# Power.net
KiCad netlist of a schematic drawn in Altium Designer
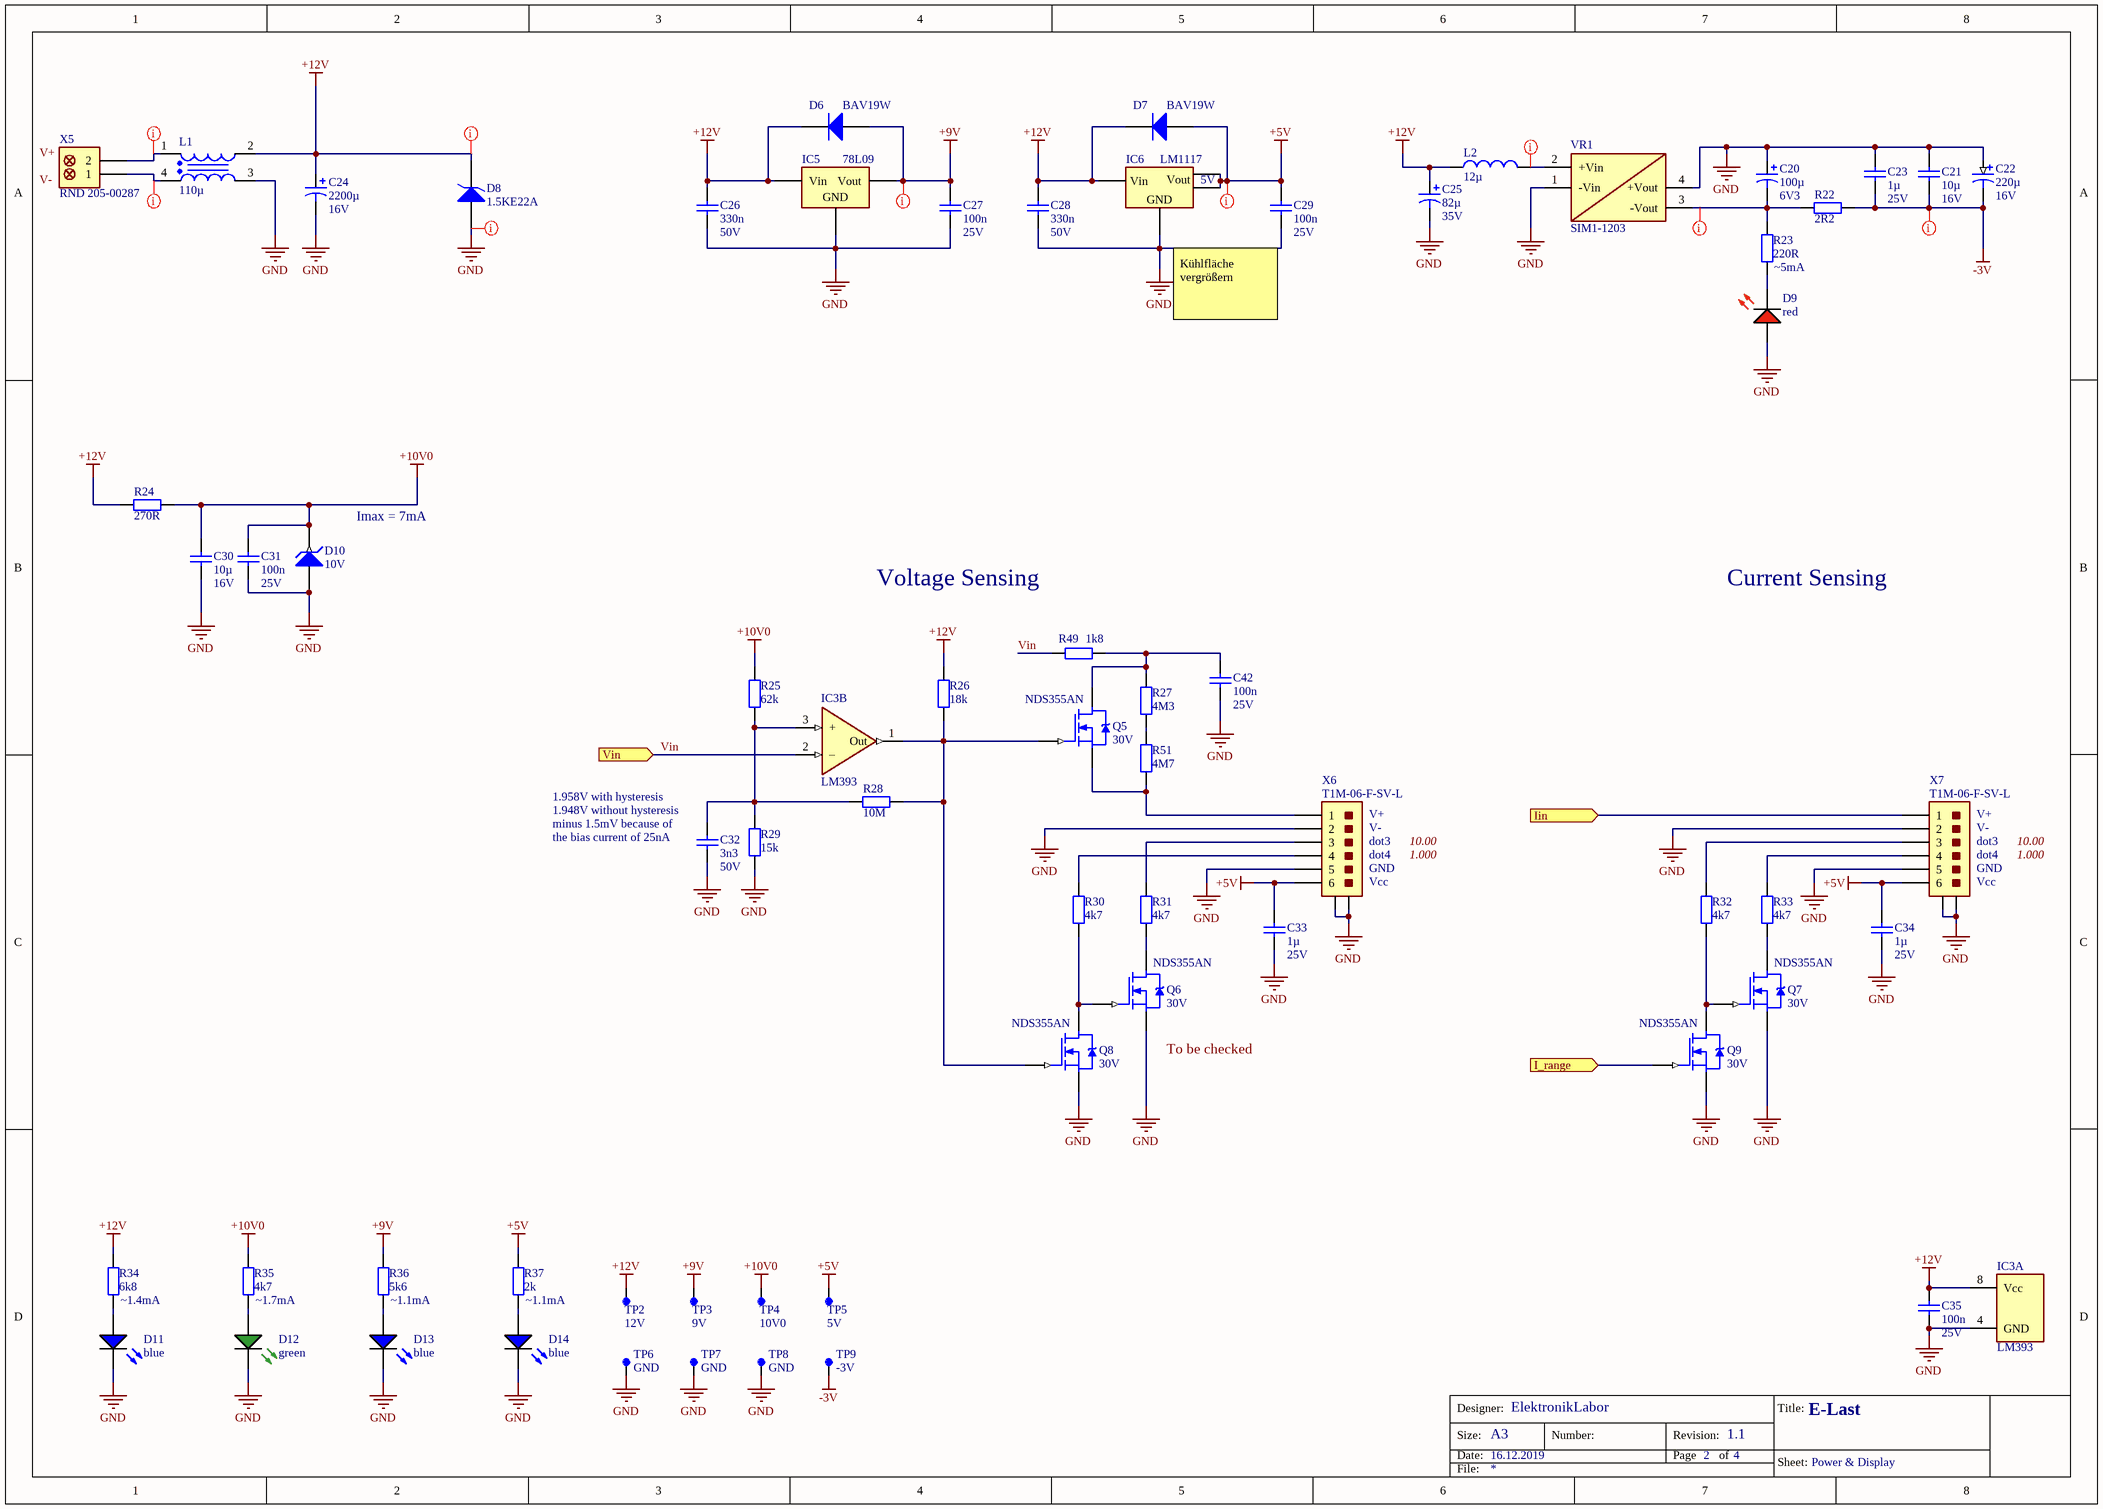
[diagram p0: Power.SchDoc]

(export (version "E")
  (design (tool "Eeschema 10.0.6"))
  (components
    (comp (ref "C20")
      (value "100µ")
      (footprint "Cap ELCO 6.3x6 mm")
      (description "Cap Elco 100µ Radial")
      (fields
        (field (name "MANUFACTURER") "Nichicon")
        (field (name "PARTNUMBER") "UMA0J101MDD")
        (field (name "VOLTAGE") "6V3")
        (field (name "COMPONENTLINK1URL") "G:\\Daten\\Datenblätter\\Kondensatoren\\Nichicon_UMA.pdf")
      )
      (libsource (lib "SchLibrary") (part "Cap Pol2 100µ"))
    )
    (comp (ref "C21")
      (value "10µ")
      (footprint "C_1206")
      (description "Cap Ceramic 1206 10µ 16V")
      (fields
        (field (name "PARTNUMBER") "CL31B106MOHNNNE")
        (field (name "MANUFACTURER") "Samsung")
        (field (name "VOLTAGE") "16V")
      )
      (libsource (lib "CustomLib") (part "C-Cer 1206 16V 10µ"))
    )
    (comp (ref "C22")
      (value "220µ")
      (footprint "Cap Tantal E (2917)")
      (description "Cap Tantal 220µ 16V SMD")
      (fields
        (field (name "MANUFACTURER") "AVX")
        (field (name "PARTNUMBER") "TPSE227*016#0100")
        (field (name "VOLTAGE") "16V")
        (field (name "COMPONENTLINK1URL") "G:\\Daten\\Datenblätter\\Kondensatoren\\AVX_Tantal_TPS.pdf")
      )
      (libsource (lib "CustomLib") (part "Cap Tantal 220µ"))
    )
    (comp (ref "C23")
      (value "1µ")
      (footprint "C_0805")
      (description "Cap Ceramic 0805 1µ 25V")
      (fields
        (field (name "MANUFACTURER") "Samsung")
        (field (name "PARTNUMBER") "CL21B105KAFNNNE")
        (field (name "VOLTAGE") "25V")
      )
      (libsource (lib "SchLibrary") (part "C-Cer 0805 1µ"))
    )
    (comp (ref "C24")
      (value "2200µ")
      (footprint "Cap ELCO 12.5x20 mm")
      (description "Cap Elco 2200µ 16V THT Radial")
      (fields
        (field (name "MANUFACTURER") "Rubycon")
        (field (name "PARTNUMBER") "UFW1C222MHD")
        (field (name "VOLTAGE") "16V")
        (field (name "COMPONENTLINK1URL") "G:\\Daten\\Datenblätter\\Kondensatoren\\Nichicon_UFW.pdf")
      )
      (libsource (lib "SchLibrary") (part "Cap Pol 2200µ 16V"))
    )
    (comp (ref "C25")
      (value "82µ")
      (footprint "Cap ELCO 6.3x15 mm")
      (description "Cap Elco 82µ Radial")
      (fields
        (field (name "MANUFACTURER") "Nippon Chemi-Con")
        (field (name "PARTNUMBER") "ELXY350ETD820MF15D")
        (field (name "VOLTAGE") "35V")
        (field (name "COMPONENTLINK1URL") "G:\\Daten\\Datenblätter\\Kondensatoren\\Chemi-Con_LXY.pdf")
      )
      (libsource (lib "SchLibrary") (part "Cap Pol2 82µ"))
    )
    (comp (ref "C26")
      (value "330n")
      (footprint "C_0805")
      (description "Cap Ceramic 0805 330n 50V")
      (fields
        (field (name "MANUFACTURER") "Samsung")
        (field (name "PARTNUMBER") "CL21B334KBFNNNE")
        (field (name "VOLTAGE") "50V")
      )
      (libsource (lib "SchLibrary") (part "C-Cer 0805 330n"))
    )
    (comp (ref "C27")
      (value "100n")
      (footprint "C_0805")
      (description "Cap Ceramic 0805 100n 25V")
      (fields (field (name "MANUFACTURER") "generic") (field (name "VOLTAGE") "25V"))
      (libsource (lib "CustomLib") (part "C-Cer 0805 100n"))
    )
    (comp (ref "C28")
      (value "330n")
      (footprint "C_0805")
      (description "Cap Ceramic 0805 330n 50V")
      (fields
        (field (name "MANUFACTURER") "Samsung")
        (field (name "PARTNUMBER") "CL21B334KBFNNNE")
        (field (name "VOLTAGE") "50V")
      )
      (libsource (lib "SchLibrary") (part "C-Cer 0805 330n"))
    )
    (comp (ref "C29")
      (value "100n")
      (footprint "C_0805")
      (description "Cap Ceramic 0805 100n 25V")
      (fields (field (name "MANUFACTURER") "generic") (field (name "VOLTAGE") "25V"))
      (libsource (lib "CustomLib") (part "C-Cer 0805 100n"))
    )
    (comp (ref "C30")
      (value "10µ")
      (footprint "C_1206")
      (description "Cap Ceramic 1206 10µ 16V")
      (fields
        (field (name "PARTNUMBER") "CL31B106MOHNNNE")
        (field (name "MANUFACTURER") "Samsung")
        (field (name "VOLTAGE") "16V")
      )
      (libsource (lib "CustomLib") (part "C-Cer 1206 16V 10µ"))
    )
    (comp (ref "C31")
      (value "100n")
      (footprint "C_0805")
      (description "Cap Ceramic 0805 100n 25V")
      (fields (field (name "MANUFACTURER") "generic") (field (name "VOLTAGE") "25V"))
      (libsource (lib "SchLibrary") (part "C-Cer 0805 100n"))
    )
    (comp (ref "C32")
      (value "3n3")
      (footprint "C_0805")
      (description "Cap Ceramic 0805 3n3 50V")
      (fields (field (name "MANUFACTURER") "generic") (field (name "VOLTAGE") "50V"))
      (libsource (lib "CustomLib") (part "C-Cer 0805 3n3"))
    )
    (comp (ref "C33")
      (value "1µ")
      (footprint "C_0805")
      (description "Cap Ceramic 0805 1µ 25V")
      (fields
        (field (name "MANUFACTURER") "Samsung")
        (field (name "PARTNUMBER") "CL21B105KAFNNNE")
        (field (name "VOLTAGE") "25V")
      )
      (libsource (lib "SchLibrary") (part "C-Cer 0805 1µ"))
    )
    (comp (ref "C34")
      (value "1µ")
      (footprint "C_0805")
      (description "Cap Ceramic 0805 1µ 25V")
      (fields
        (field (name "MANUFACTURER") "Samsung")
        (field (name "PARTNUMBER") "CL21B105KAFNNNE")
        (field (name "VOLTAGE") "25V")
      )
      (libsource (lib "SchLibrary") (part "C-Cer 0805 1µ"))
    )
    (comp (ref "C35")
      (value "100n")
      (footprint "C_0805")
      (description "Cap Ceramic 0805 100n 25V")
      (fields (field (name "MANUFACTURER") "generic") (field (name "VOLTAGE") "25V"))
      (libsource (lib "SchLibrary") (part "C-Cer 0805 100n"))
    )
    (comp (ref "C42")
      (value "100n")
      (footprint "C_0805")
      (description "Cap Ceramic 0805 100n 25V")
      (fields (field (name "MANUFACTURER") "generic") (field (name "VOLTAGE") "25V"))
      (libsource (lib "SchLibrary") (part "C-Cer 0805 100n"))
    )
    (comp (ref "D6")
      (value "BAV19W")
      (footprint "SOD-123")
      (description "Diode, Fast, 400mA, SOD-123, SMD")
      (fields
        (field (name "MANUFACTURER") "Diodes")
        (field (name "PARTNUMBER") "BAV19W-E3-08")
        (field (name "COMPONENTLINK1URL") "G:\\Daten\\Datenblätter\\Dioden\\BAV19W.pdf")
      )
      (libsource (lib "CustomLib") (part "Diode BAV19W"))
    )
    (comp (ref "D7")
      (value "BAV19W")
      (footprint "SOD-123")
      (description "Diode, Fast, 400mA, SOD-123, SMD")
      (fields
        (field (name "MANUFACTURER") "Diodes")
        (field (name "PARTNUMBER") "BAV19W-E3-08")
        (field (name "COMPONENTLINK1URL") "G:\\Daten\\Datenblätter\\Dioden\\BAV19W.pdf")
      )
      (libsource (lib "CustomLib") (part "Diode BAV19W"))
    )
    (comp (ref "D8")
      (value "1.5KE22A")
      (footprint "DO-201AD Vert")
      (description "Diode, TVS, Uni, 22V, CB429, THT")
      (fields
        (field (name "MANUFACTURER") "ST")
        (field (name "VOLTAGE") "18.8V")
        (field (name "COMPONENTLINK1URL") "G:\\Daten\\Datenblätter\\Dioden\\1_5KE22A_TVS.pdf")
      )
      (libsource (lib "CustomLib") (part "Diode 1.5KE22A"))
    )
    (comp (ref "D9")
      (value "red")
      (footprint "LED 0805 SMD WL-SMCW")
      (description "LED Red 0805 SMD")
      (fields
        (field (name "MANUFACTURER") "Würth Elektronik")
        (field (name "PARTNUMBER") "150080SS75000")
        (field (name "COMPONENTLINK1URL") "G:\\Daten\\Datenblätter\\LED\\0805_red_150080SS75000.pdf")
      )
      (libsource (lib "SchLibrary") (part "LED Red 0805 SMD"))
    )
    (comp (ref "D10")
      (value "10V")
      (footprint "SOT23_N")
      (description "V-Ref LM4040AIM3-10.0")
      (fields
        (field (name "PARTNUMBER") "LM4040AIM3-10.0/NOPB")
        (field (name "MANUFACTURER") "Texas Instruments")
        (field (name "COMPONENTLINK1URL") "G:\\Daten\\Datenblätter\\Spg.-Referenz\\TI_LM4040-N.pdf")
      )
      (libsource (lib "SchLibrary") (part "V-Ref LM4040AIM3-10.0"))
    )
    (comp (ref "D11")
      (value "blue")
      (footprint "LED 0805 SMD WL-SMCW")
      (description "LED Blue 0805 SMD")
      (fields
        (field (name "MANUFACTURER") "Würth Elektronik")
        (field (name "PARTNUMBER") "150080BS75000")
        (field (name "COMPONENTLINK1URL") "G:\\Daten\\Datenblätter\\LED\\0805_blue_150080BS75000.pdf")
      )
      (libsource (lib "SchLibrary") (part "LED Blue 0805 SMD"))
    )
    (comp (ref "D12")
      (value "green")
      (footprint "LED 0805 SMD WL-SMCW")
      (description "LED Green 0805 SMD")
      (fields (field (name "PARTNUMBER") "Generic") (field (name "VOLTAGE") "1.886V"))
      (libsource (lib "CustomLib") (part "LED Green 0805 SMD"))
    )
    (comp (ref "D13")
      (value "blue")
      (footprint "LED 0805 SMD WL-SMCW")
      (description "LED Blue 0805 SMD")
      (fields
        (field (name "MANUFACTURER") "Würth Elektronik")
        (field (name "PARTNUMBER") "150080BS75000")
        (field (name "COMPONENTLINK1URL") "G:\\Daten\\Datenblätter\\LED\\0805_blue_150080BS75000.pdf")
      )
      (libsource (lib "SchLibrary") (part "LED Blue 0805 SMD"))
    )
    (comp (ref "D14")
      (value "blue")
      (footprint "LED 0805 SMD WL-SMCW")
      (description "LED Blue 0805 SMD")
      (fields
        (field (name "MANUFACTURER") "Würth Elektronik")
        (field (name "PARTNUMBER") "150080BS75000")
        (field (name "COMPONENTLINK1URL") "G:\\Daten\\Datenblätter\\LED\\0805_blue_150080BS75000.pdf")
      )
      (libsource (lib "SchLibrary") (part "LED Blue 0805 SMD"))
    )
    (comp (ref "IC3")
      (value "LM393")
      (footprint "SOIC8_N")
      (description "Comparator LM393DT 2x")
      (fields
        (field (name "MANUFACTURER") "ST")
        (field (name "PARTNUMBER") "LM393DT")
        (field (name "COMPONENTLINK1URL") "G:\\Daten\\Datenblätter\\Komparatoren\\ST_LM393.pdf")
      )
      (libsource (lib "SchLibrary") (part "LM393DT"))
    )
    (comp (ref "IC5")
      (value "78L09")
      (footprint "TO-92A")
      (description "Voltage Regulator 9V")
      (fields
        (field (name "MANUFACTURER") "ST")
        (field (name "PARTNUMBER") "L78L09ACZ")
        (field (name "COMPONENTLINK1URL") "G:\\Daten\\Datenblätter\\Spannungsregler\\78L09_ST.pdf")
      )
      (libsource (lib "CustomLib") (part "Volt Reg 78L09 TO92"))
    )
    (comp (ref "IC6")
      (value "LM1117")
      (footprint "SOT-223")
      (description "Voltage Regulator 5V SOT-223")
      (fields
        (field (name "MANUFACTURER") "Texas Instruments")
        (field (name "PARTNUMBER") "L7805CV")
        (field (name "VOLTAGE") "5V")
        (field (name "COMPONENTLINK1URL") "G:\\Daten\\Datenblätter\\Spannungsregler\\LM1117.pdf")
      )
      (libsource (lib "CustomLib") (part "Volt Reg LM1117MPX-5.0 SOT-223"))
    )
    (comp (ref "L1")
      (value "110µ")
      (footprint "CMC WE-CMB Type S")
      (description "Common Mode Choke, WE-CMB Type S, 110 uH")
      (fields (field (name "MANUFACTURER") "Würth Elektronik") (field (name "PARTNUMBER") "744842311"))
      (libsource (lib "CustomLib") (part "CMC 110µ"))
    )
    (comp (ref "L2")
      (value "12µ")
      (footprint "WE-GFH 4532")
      (description "Inductor 12µ 7447669112 SMD")
      (fields
        (field (name "PARTNUMBER") "7447669112")
        (field (name "MANUFACTURER") "Würth Elektronik")
        (field (name "COMPONENTLINK1URL") "G:\\Daten\\Datenblätter\\Inductors\\WE_7447669112_12µ.pdf")
      )
      (libsource (lib "SchLibrary") (part "Inductor 12µ"))
    )
    (comp (ref "Q5")
      (value "NDS355AN")
      (footprint "SOT23_N - n-MOS")
      (description "Transistor n-MOS SOT-23 30V Vgs=20V")
      (fields
        (field (name "MANUFACTURER") "ON Semiconductor")
        (field (name "VOLTAGE") "30V")
        (field (name "COMPONENTLINK1URL") "G:\\Daten\\Datenblätter\\Transistoren\\nMOS_NDS355AN.pdf")
      )
      (libsource (lib "SchLibrary") (part "Transistor n-MOS NDS355AN"))
    )
    (comp (ref "Q6")
      (value "NDS355AN")
      (footprint "SOT23_N - n-MOS")
      (description "Transistor n-MOS SOT-23 30V Vgs=20V")
      (fields
        (field (name "MANUFACTURER") "ON Semiconductor")
        (field (name "VOLTAGE") "30V")
        (field (name "COMPONENTLINK1URL") "G:\\Daten\\Datenblätter\\Transistoren\\nMOS_NDS355AN.pdf")
      )
      (libsource (lib "SchLibrary") (part "Transistor n-MOS NDS355AN"))
    )
    (comp (ref "Q7")
      (value "NDS355AN")
      (footprint "SOT23_N - n-MOS")
      (description "Transistor n-MOS SOT-23 30V Vgs=20V")
      (fields
        (field (name "MANUFACTURER") "ON Semiconductor")
        (field (name "VOLTAGE") "30V")
        (field (name "COMPONENTLINK1URL") "G:\\Daten\\Datenblätter\\Transistoren\\nMOS_NDS355AN.pdf")
      )
      (libsource (lib "SchLibrary") (part "Transistor n-MOS NDS355AN"))
    )
    (comp (ref "Q8")
      (value "NDS355AN")
      (footprint "SOT23_N - n-MOS")
      (description "Transistor n-MOS SOT-23 30V Vgs=20V")
      (fields
        (field (name "MANUFACTURER") "ON Semiconductor")
        (field (name "VOLTAGE") "30V")
        (field (name "COMPONENTLINK1URL") "G:\\Daten\\Datenblätter\\Transistoren\\nMOS_NDS355AN.pdf")
      )
      (libsource (lib "SchLibrary") (part "Transistor n-MOS NDS355AN"))
    )
    (comp (ref "Q9")
      (value "NDS355AN")
      (footprint "SOT23_N - n-MOS")
      (description "Transistor n-MOS SOT-23 30V Vgs=20V")
      (fields
        (field (name "MANUFACTURER") "ON Semiconductor")
        (field (name "VOLTAGE") "30V")
        (field (name "COMPONENTLINK1URL") "G:\\Daten\\Datenblätter\\Transistoren\\nMOS_NDS355AN.pdf")
      )
      (libsource (lib "SchLibrary") (part "Transistor n-MOS NDS355AN"))
    )
    (comp (ref "R22")
      (value "2R2")
      (footprint "Res 0805")
      (description "Resistor 0805 2R2")
      (fields (field (name "MANUFACTURER") "generic") (field (name "POWER") "0.125W"))
      (libsource (lib "SchLibrary") (part "Res 0805 2R2"))
    )
    (comp (ref "R23")
      (value "220R")
      (footprint "Res 0805")
      (description "Resistor 0805 220R")
      (fields (field (name "MANUFACTURER") "generic") (field (name "POWER") "0.125W"))
      (libsource (lib "SchLibrary") (part "Res 0805 220R"))
    )
    (comp (ref "R24")
      (value "270R")
      (footprint "Res 0805")
      (description "Resistor 0805 270R")
      (fields (field (name "MANUFACTURER") "generic") (field (name "POWER") "0.125W"))
      (libsource (lib "SchLibrary") (part "Res 0805 270R"))
    )
    (comp (ref "R25")
      (value "62k")
      (footprint "Res 0805")
      (description "Resistor 0805 62k")
      (fields (field (name "MANUFACTURER") "generic") (field (name "POWER") "0.125W"))
      (libsource (lib "SchLibrary") (part "Res 0805 62k"))
    )
    (comp (ref "R26")
      (value "18k")
      (footprint "Res 0805")
      (description "Resistor 0805 18k")
      (fields (field (name "MANUFACTURER") "generic") (field (name "POWER") "0.125W"))
      (libsource (lib "SchLibrary") (part "Res 0805 18k"))
    )
    (comp (ref "R27")
      (value "4M3")
      (footprint "Res 0805")
      (description "Resistor 0805 4M3")
      (fields (field (name "MANUFACTURER") "generic") (field (name "POWER") "0.125W"))
      (libsource (lib "CustomLib") (part "Res 0805 4M3"))
    )
    (comp (ref "R28")
      (value "10M")
      (footprint "Res 0805")
      (description "Resistor 0805 10M")
      (fields (field (name "MANUFACTURER") "generic") (field (name "POWER") "0.125W"))
      (libsource (lib "SchLibrary") (part "Res 0805 10M"))
    )
    (comp (ref "R29")
      (value "15k")
      (footprint "Res 0805")
      (description "Resistor 0805 15k")
      (fields (field (name "MANUFACTURER") "generic") (field (name "POWER") "0.125W"))
      (libsource (lib "SchLibrary") (part "Res 0805 15k"))
    )
    (comp (ref "R30")
      (value "4k7")
      (footprint "Res 0805")
      (description "Resistor 0805 4k7")
      (fields (field (name "MANUFACTURER") "generic") (field (name "POWER") "0.125W"))
      (libsource (lib "SchLibrary") (part "Res 0805 4k7"))
    )
    (comp (ref "R31")
      (value "4k7")
      (footprint "Res 0805")
      (description "Resistor 0805 4k7")
      (fields (field (name "MANUFACTURER") "generic") (field (name "POWER") "0.125W"))
      (libsource (lib "SchLibrary") (part "Res 0805 4k7"))
    )
    (comp (ref "R32")
      (value "4k7")
      (footprint "Res 0805")
      (description "Resistor 0805 4k7")
      (fields (field (name "MANUFACTURER") "generic") (field (name "POWER") "0.125W"))
      (libsource (lib "SchLibrary") (part "Res 0805 4k7"))
    )
    (comp (ref "R33")
      (value "4k7")
      (footprint "Res 0805")
      (description "Resistor 0805 4k7")
      (fields (field (name "MANUFACTURER") "generic") (field (name "POWER") "0.125W"))
      (libsource (lib "") (part "Res 0805 4k7_1"))
    )
    (comp (ref "R34")
      (value "6k8")
      (footprint "Res 0805")
      (description "Resistor 0805 6k8")
      (fields (field (name "MANUFACTURER") "generic") (field (name "POWER") "0.125W"))
      (libsource (lib "CustomLib") (part "Res 0805 6k8"))
    )
    (comp (ref "R35")
      (value "4k7")
      (footprint "Res 0805")
      (description "Resistor 0805 4k7")
      (fields (field (name "MANUFACTURER") "generic") (field (name "POWER") "0.125W"))
      (libsource (lib "SchLibrary") (part "Res 0805 4k7"))
    )
    (comp (ref "R36")
      (value "5k6")
      (footprint "Res 0805")
      (description "Resistor 0805 5k6")
      (fields (field (name "MANUFACTURER") "generic") (field (name "POWER") "0.125W"))
      (libsource (lib "CustomLib") (part "Res 0805 5k6"))
    )
    (comp (ref "R37")
      (value "2k")
      (footprint "Res 0805")
      (description "Resistor 0805 2k")
      (fields (field (name "MANUFACTURER") "generic") (field (name "POWER") "0.125W"))
      (libsource (lib "CustomLib") (part "Res 0805 2k"))
    )
    (comp (ref "R49")
      (value "1k8")
      (footprint "Res 0805")
      (description "Resistor 0805 1k8")
      (fields (field (name "MANUFACTURER") "generic") (field (name "POWER") "0.125W"))
      (libsource (lib "CustomLib") (part "Res 0805 1k8"))
    )
    (comp (ref "R51")
      (value "4M7")
      (footprint "Res 0805")
      (description "Resistor 0805 4M7")
      (fields (field (name "MANUFACTURER") "generic") (field (name "POWER") "0.125W"))
      (libsource (lib "CustomLib") (part "Res 0805 4M7"))
    )
    (comp (ref "TP2")
      (value "12V")
      (footprint "Test Point SMD Rnd 1mm")
      (description "Test Point")
      (libsource (lib "CustomLib") (part "Test Point"))
    )
    (comp (ref "TP3")
      (value "9V")
      (footprint "Test Point SMD Rnd 1mm")
      (description "Test Point")
      (libsource (lib "CustomLib") (part "Test Point"))
    )
    (comp (ref "TP4")
      (value "10V0")
      (footprint "Test Point SMD Rnd 1mm")
      (description "Test Point")
      (libsource (lib "CustomLib") (part "Test Point"))
    )
    (comp (ref "TP5")
      (value "5V")
      (footprint "Test Point SMD Rnd 1mm")
      (description "Test Point")
      (libsource (lib "CustomLib") (part "Test Point"))
    )
    (comp (ref "TP6")
      (value "GND")
      (footprint "Test Point SMD Rnd 1mm")
      (description "Test Point")
      (libsource (lib "CustomLib") (part "Test Point"))
    )
    (comp (ref "TP7")
      (value "GND")
      (footprint "Test Point SMD Rnd 1mm")
      (description "Test Point")
      (libsource (lib "CustomLib") (part "Test Point"))
    )
    (comp (ref "TP8")
      (value "GND")
      (footprint "Test Point SMD Rnd 1mm")
      (description "Test Point")
      (libsource (lib "CustomLib") (part "Test Point"))
    )
    (comp (ref "TP9")
      (value "-3V")
      (footprint "Test Point SMD Rnd 1mm")
      (description "Test Point")
      (libsource (lib "CustomLib") (part "Test Point"))
    )
    (comp (ref "VR1")
      (value "SIM1-1203")
      (footprint "SIL-4")
      (description "DC/DC Converter Isolated 3V")
      (fields
        (field (name "MANUFACTURER") "HN Electronic Components")
        (field (name "PARTNUMBER") "SIM1-1203-SIL4")
        (field (name "COMPONENTLINK1URL") "G:\\Daten\\Datenblätter\\DCDC_Converter\\SIM1_1203.pdf")
      )
      (libsource (lib "SchLibrary") (part "DC/DC SIM1-1203"))
    )
    (comp (ref "X5")
      (value "RND 205-00287")
      (footprint "TRMNL 5.08mm 2x")
      (description "Terminal, 2-Pin, 5.08mm, THT")
      (fields
        (field (name "MANUFACTURER") "RND connect")
        (field (name "COMPONENTLINK2URL") "G:\\Daten\\Datenblätter\\Verbinder\\Terminal_RND_205-00287.pdf")
      )
      (libsource (lib "SchLibrary") (part "Termial 2pin 5.08mm"))
    )
    (comp (ref "X6")
      (value "T1M-06-F-SV-L")
      (footprint "T1M-06-XX-S-V")
      (description "Connector, Male, Vertical, 6-Pin, 1mm, SMD")
      (fields
        (field (name "MANUFACTURER") "SAMTEC")
        (field (name "MATINGPARTNUMBER") "S1SS-06-L")
        (field (name "COMPONENTLINK1URL") "G:\\Daten\\Datenblätter\\Steckverbinder\\T1M-Single-Row.pdf")
      )
      (libsource (lib "SchLibrary") (part "Con Male 6-Pin"))
    )
    (comp (ref "X7")
      (value "T1M-06-F-SV-L")
      (footprint "T1M-06-XX-S-V")
      (description "Connector, Male, Vertical, 6-Pin, 1mm, SMD")
      (fields
        (field (name "MANUFACTURER") "SAMTEC")
        (field (name "MATINGPARTNUMBER") "S1SS-06-L")
        (field (name "COMPONENTLINK1URL") "G:\\Daten\\Datenblätter\\Steckverbinder\\T1M-Single-Row.pdf")
      )
      (libsource (lib "SchLibrary") (part "Con Male 6-Pin"))
    )
  )
  (nets
    (net (code "1") (name "+5V") (class "Default")
      (node (ref "C29") (pin "1") (pinfunction "1_1") (pintype "passive"))
      (node (ref "C33") (pin "1") (pinfunction "1_1") (pintype "passive"))
      (node (ref "C34") (pin "1") (pinfunction "1_1") (pintype "passive"))
      (node (ref "D7") (pin "1") (pinfunction "A_1") (pintype "passive"))
      (node (ref "IC6") (pin "2") (pinfunction "Vout_2") (pintype "power_in"))
      (node (ref "IC6") (pin "4") (pinfunction "Vout_4") (pintype "power_in"))
      (node (ref "R37") (pin "1") (pinfunction "1_1") (pintype "passive"))
      (node (ref "TP5") (pin "1") (pinfunction "1_1") (pintype "passive"))
      (node (ref "X6") (pin "6") (pinfunction "6_6") (pintype "passive"))
      (node (ref "X7") (pin "6") (pinfunction "6_6") (pintype "passive"))
    )
    (net (code "2") (name "+9V") (class "Default")
      (node (ref "C27") (pin "1") (pinfunction "1_1") (pintype "passive"))
      (node (ref "D6") (pin "1") (pinfunction "A_1") (pintype "passive"))
      (node (ref "IC5") (pin "1") (pinfunction "Vout_1") (pintype "power_in"))
      (node (ref "R36") (pin "1") (pinfunction "1_1") (pintype "passive"))
      (node (ref "TP3") (pin "1") (pinfunction "1_1") (pintype "passive"))
    )
    (net (code "3") (name "+10V0") (class "Default")
      (node (ref "C30") (pin "1") (pinfunction "1_1") (pintype "passive"))
      (node (ref "C31") (pin "1") (pinfunction "1_1") (pintype "passive"))
      (node (ref "D10") (pin "1") (pinfunction "K_1") (pintype "output"))
      (node (ref "R24") (pin "2") (pinfunction "2_2") (pintype "passive"))
      (node (ref "R25") (pin "1") (pinfunction "1_1") (pintype "passive"))
      (node (ref "R35") (pin "1") (pinfunction "1_1") (pintype "passive"))
      (node (ref "TP4") (pin "1") (pinfunction "1_1") (pintype "passive"))
    )
    (net (code "4") (name "+12V") (class "Default")
      (node (ref "C24") (pin "1") (pinfunction "1_1") (pintype "passive"))
      (node (ref "C25") (pin "1") (pinfunction "1_1") (pintype "passive"))
      (node (ref "C26") (pin "1") (pinfunction "1_1") (pintype "passive"))
      (node (ref "C28") (pin "1") (pinfunction "1_1") (pintype "passive"))
      (node (ref "C35") (pin "1") (pinfunction "1_1") (pintype "passive"))
      (node (ref "D6") (pin "2") (pinfunction "K_2") (pintype "passive"))
      (node (ref "D7") (pin "2") (pinfunction "K_2") (pintype "passive"))
      (node (ref "D8") (pin "K") (pinfunction "K_K") (pintype "passive"))
      (node (ref "IC3") (pin "8") (pinfunction "Vcc_8") (pintype "power_in"))
      (node (ref "IC5") (pin "3") (pinfunction "Vin_3") (pintype "power_in"))
      (node (ref "IC6") (pin "3") (pinfunction "Vin_3") (pintype "power_in"))
      (node (ref "L1") (pin "2") (pinfunction "2_2") (pintype "passive"))
      (node (ref "L2") (pin "1") (pinfunction "1_1") (pintype "passive"))
      (node (ref "R24") (pin "1") (pinfunction "1_1") (pintype "passive"))
      (node (ref "R26") (pin "1") (pinfunction "1_1") (pintype "passive"))
      (node (ref "R34") (pin "1") (pinfunction "1_1") (pintype "passive"))
      (node (ref "TP2") (pin "1") (pinfunction "1_1") (pintype "passive"))
    )
    (net (code "5") (name "-3V") (class "Default")
      (node (ref "C21") (pin "2") (pinfunction "2_2") (pintype "passive"))
      (node (ref "C22") (pin "2") (pinfunction "2_2") (pintype "power_in"))
      (node (ref "C23") (pin "2") (pinfunction "2_2") (pintype "passive"))
      (node (ref "R22") (pin "2") (pinfunction "2_2") (pintype "passive"))
      (node (ref "TP9") (pin "1") (pinfunction "1_1") (pintype "passive"))
    )
    (net (code "6") (name "/I_range") (class "Default")
      (node (ref "Q9") (pin "1") (pinfunction "G_1") (pintype "input"))
    )
    (net (code "7") (name "/Iin") (class "Default")
      (node (ref "X7") (pin "1") (pinfunction "1_1") (pintype "passive"))
    )
    (net (code "8") (name "/Vin") (class "Default")
      (node (ref "IC3") (pin "2") (pinfunction "–_2") (pintype "input"))
      (node (ref "R49") (pin "2") (pinfunction "2_2") (pintype "passive"))
    )
    (net (code "9") (name "GND") (class "Default")
      (node (ref "C20") (pin "1") (pinfunction "1_1") (pintype "passive"))
      (node (ref "C21") (pin "1") (pinfunction "1_1") (pintype "passive"))
      (node (ref "C22") (pin "1") (pinfunction "1_1") (pintype "input"))
      (node (ref "C23") (pin "1") (pinfunction "1_1") (pintype "passive"))
      (node (ref "C24") (pin "2") (pinfunction "2_2") (pintype "passive"))
      (node (ref "C25") (pin "2") (pinfunction "2_2") (pintype "passive"))
      (node (ref "C26") (pin "2") (pinfunction "2_2") (pintype "passive"))
      (node (ref "C27") (pin "2") (pinfunction "2_2") (pintype "passive"))
      (node (ref "C28") (pin "2") (pinfunction "2_2") (pintype "passive"))
      (node (ref "C29") (pin "2") (pinfunction "2_2") (pintype "passive"))
      (node (ref "C30") (pin "2") (pinfunction "2_2") (pintype "passive"))
      (node (ref "C31") (pin "2") (pinfunction "2_2") (pintype "passive"))
      (node (ref "C32") (pin "2") (pinfunction "2_2") (pintype "passive"))
      (node (ref "C33") (pin "2") (pinfunction "2_2") (pintype "passive"))
      (node (ref "C34") (pin "2") (pinfunction "2_2") (pintype "passive"))
      (node (ref "C35") (pin "2") (pinfunction "2_2") (pintype "passive"))
      (node (ref "C42") (pin "2") (pinfunction "2_2") (pintype "passive"))
      (node (ref "D10") (pin "2") (pinfunction "A_2") (pintype "power_in"))
      (node (ref "D11") (pin "1") (pinfunction "K_1") (pintype "passive"))
      (node (ref "D12") (pin "1") (pinfunction "K_1") (pintype "passive"))
      (node (ref "D13") (pin "1") (pinfunction "K_1") (pintype "passive"))
      (node (ref "D14") (pin "1") (pinfunction "K_1") (pintype "passive"))
      (node (ref "D8") (pin "A") (pinfunction "A_A") (pintype "passive"))
      (node (ref "D9") (pin "2") (pinfunction "A_2") (pintype "passive"))
      (node (ref "IC3") (pin "4") (pinfunction "GND_4") (pintype "passive"))
      (node (ref "IC5") (pin "2") (pinfunction "GND_2") (pintype "passive"))
      (node (ref "IC6") (pin "1") (pinfunction "GND_1") (pintype "passive"))
      (node (ref "L1") (pin "3") (pinfunction "3_3") (pintype "passive"))
      (node (ref "Q6") (pin "2") (pinfunction "S_2") (pintype "passive"))
      (node (ref "Q7") (pin "2") (pinfunction "S_2") (pintype "passive"))
      (node (ref "Q8") (pin "2") (pinfunction "S_2") (pintype "passive"))
      (node (ref "Q9") (pin "2") (pinfunction "S_2") (pintype "passive"))
      (node (ref "R29") (pin "2") (pinfunction "2_2") (pintype "passive"))
      (node (ref "TP6") (pin "1") (pinfunction "1_1") (pintype "passive"))
      (node (ref "TP7") (pin "1") (pinfunction "1_1") (pintype "passive"))
      (node (ref "TP8") (pin "1") (pinfunction "1_1") (pintype "passive"))
      (node (ref "VR1") (pin "1") (pinfunction "-Vin_1") (pintype "power_in"))
      (node (ref "VR1") (pin "4") (pinfunction "+Vout_4") (pintype "power_in"))
      (node (ref "X6") (pin "2") (pinfunction "2_2") (pintype "passive"))
      (node (ref "X6") (pin "5") (pinfunction "5_5") (pintype "passive"))
      (node (ref "X6") (pin "7") (pinfunction "CASE_7") (pintype "passive"))
      (node (ref "X6") (pin "8") (pinfunction "CASE_8") (pintype "passive"))
      (node (ref "X7") (pin "2") (pinfunction "2_2") (pintype "passive"))
      (node (ref "X7") (pin "5") (pinfunction "5_5") (pintype "passive"))
      (node (ref "X7") (pin "7") (pinfunction "CASE_7") (pintype "passive"))
      (node (ref "X7") (pin "8") (pinfunction "CASE_8") (pintype "passive"))
    )
    (net (code "10") (name "Net-(D9-K)") (class "Default")
      (node (ref "D9") (pin "1") (pinfunction "K_1") (pintype "passive"))
      (node (ref "R23") (pin "2") (pinfunction "2_2") (pintype "passive"))
    )
    (net (code "11") (name "Net-(D11-A)") (class "Default")
      (node (ref "D11") (pin "2") (pinfunction "A_2") (pintype "passive"))
      (node (ref "R34") (pin "2") (pinfunction "2_2") (pintype "passive"))
    )
    (net (code "12") (name "Net-(D12-A)") (class "Default")
      (node (ref "D12") (pin "2") (pinfunction "A_2") (pintype "passive"))
      (node (ref "R35") (pin "2") (pinfunction "2_2") (pintype "passive"))
    )
    (net (code "13") (name "Net-(D13-A)") (class "Default")
      (node (ref "D13") (pin "2") (pinfunction "A_2") (pintype "passive"))
      (node (ref "R36") (pin "2") (pinfunction "2_2") (pintype "passive"))
    )
    (net (code "14") (name "Net-(D14-A)") (class "Default")
      (node (ref "D14") (pin "2") (pinfunction "A_2") (pintype "passive"))
      (node (ref "R37") (pin "2") (pinfunction "2_2") (pintype "passive"))
    )
    (net (code "15") (name "Net-(IC3B-+)") (class "Default")
      (node (ref "C32") (pin "1") (pinfunction "1_1") (pintype "passive"))
      (node (ref "IC3") (pin "3") (pinfunction "+_3") (pintype "input"))
      (node (ref "R25") (pin "2") (pinfunction "2_2") (pintype "passive"))
      (node (ref "R28") (pin "1") (pinfunction "1_1") (pintype "passive"))
      (node (ref "R29") (pin "1") (pinfunction "1_1") (pintype "passive"))
    )
    (net (code "16") (name "Net-(IC3B-Out)") (class "Default")
      (node (ref "IC3") (pin "1") (pinfunction "Out_1") (pintype "output"))
      (node (ref "Q5") (pin "1") (pinfunction "G_1") (pintype "input"))
      (node (ref "Q8") (pin "1") (pinfunction "G_1") (pintype "input"))
      (node (ref "R26") (pin "2") (pinfunction "2_2") (pintype "passive"))
      (node (ref "R28") (pin "2") (pinfunction "2_2") (pintype "passive"))
    )
    (net (code "17") (name "Net-(L1-Pad1)") (class "Default")
      (node (ref "L1") (pin "1") (pinfunction "1_1") (pintype "passive"))
      (node (ref "X5") (pin "2") (pinfunction "2_2") (pintype "passive"))
    )
    (net (code "18") (name "Net-(L1-Pad4)") (class "Default")
      (node (ref "L1") (pin "4") (pinfunction "4_4") (pintype "passive"))
      (node (ref "X5") (pin "1") (pinfunction "1_1") (pintype "passive"))
    )
    (net (code "19") (name "Net-(Q5-D)") (class "Default")
      (node (ref "C42") (pin "1") (pinfunction "1_1") (pintype "passive"))
      (node (ref "Q5") (pin "3") (pinfunction "D_3") (pintype "passive"))
      (node (ref "R27") (pin "2") (pinfunction "2_2") (pintype "passive"))
      (node (ref "R49") (pin "1") (pinfunction "1_1") (pintype "passive"))
    )
    (net (code "20") (name "Net-(Q5-S)") (class "Default")
      (node (ref "Q5") (pin "2") (pinfunction "S_2") (pintype "passive"))
      (node (ref "R51") (pin "2") (pinfunction "2_2") (pintype "passive"))
      (node (ref "X6") (pin "1") (pinfunction "1_1") (pintype "passive"))
    )
    (net (code "21") (name "Net-(Q6-D)") (class "Default")
      (node (ref "Q6") (pin "3") (pinfunction "D_3") (pintype "passive"))
      (node (ref "R31") (pin "2") (pinfunction "2_2") (pintype "passive"))
    )
    (net (code "22") (name "Net-(Q6-G)") (class "Default")
      (node (ref "Q6") (pin "1") (pinfunction "G_1") (pintype "input"))
      (node (ref "Q8") (pin "3") (pinfunction "D_3") (pintype "passive"))
      (node (ref "R30") (pin "2") (pinfunction "2_2") (pintype "passive"))
    )
    (net (code "23") (name "Net-(Q7-D)") (class "Default")
      (node (ref "Q7") (pin "3") (pinfunction "D_3") (pintype "passive"))
      (node (ref "R33") (pin "1") (pinfunction "1_1") (pintype "passive"))
    )
    (net (code "24") (name "Net-(Q7-G)") (class "Default")
      (node (ref "Q7") (pin "1") (pinfunction "G_1") (pintype "input"))
      (node (ref "Q9") (pin "3") (pinfunction "D_3") (pintype "passive"))
      (node (ref "R32") (pin "2") (pinfunction "2_2") (pintype "passive"))
    )
    (net (code "25") (name "Net-(R27-Pad1)") (class "Default")
      (node (ref "R27") (pin "1") (pinfunction "1_1") (pintype "passive"))
      (node (ref "R51") (pin "1") (pinfunction "1_1") (pintype "passive"))
    )
    (net (code "26") (name "Net-(R30-Pad1)") (class "Default")
      (node (ref "R30") (pin "1") (pinfunction "1_1") (pintype "passive"))
      (node (ref "X6") (pin "4") (pinfunction "4_4") (pintype "passive"))
    )
    (net (code "27") (name "Net-(R31-Pad1)") (class "Default")
      (node (ref "R31") (pin "1") (pinfunction "1_1") (pintype "passive"))
      (node (ref "X6") (pin "3") (pinfunction "3_3") (pintype "passive"))
    )
    (net (code "28") (name "Net-(R32-Pad1)") (class "Default")
      (node (ref "R32") (pin "1") (pinfunction "1_1") (pintype "passive"))
      (node (ref "X7") (pin "3") (pinfunction "3_3") (pintype "passive"))
    )
    (net (code "29") (name "Net-(R33-Pad2)") (class "Default")
      (node (ref "R33") (pin "2") (pinfunction "2_2") (pintype "passive"))
      (node (ref "X7") (pin "4") (pinfunction "4_4") (pintype "passive"))
    )
    (net (code "30") (name "Net-(VR1-+Vin)") (class "Default")
      (node (ref "L2") (pin "2") (pinfunction "2_2") (pintype "passive"))
      (node (ref "VR1") (pin "2") (pinfunction "+Vin_2") (pintype "power_in"))
    )
    (net (code "31") (name "Net-(VR1--Vout)") (class "Default")
      (node (ref "C20") (pin "2") (pinfunction "2_2") (pintype "passive"))
      (node (ref "R22") (pin "1") (pinfunction "1_1") (pintype "passive"))
      (node (ref "R23") (pin "1") (pinfunction "1_1") (pintype "passive"))
      (node (ref "VR1") (pin "3") (pinfunction "-Vout_3") (pintype "power_in"))
    )
  )
)
